# SCH_555__2022-11-10.net
KiCad netlist of a schematic drawn in EasyEDA
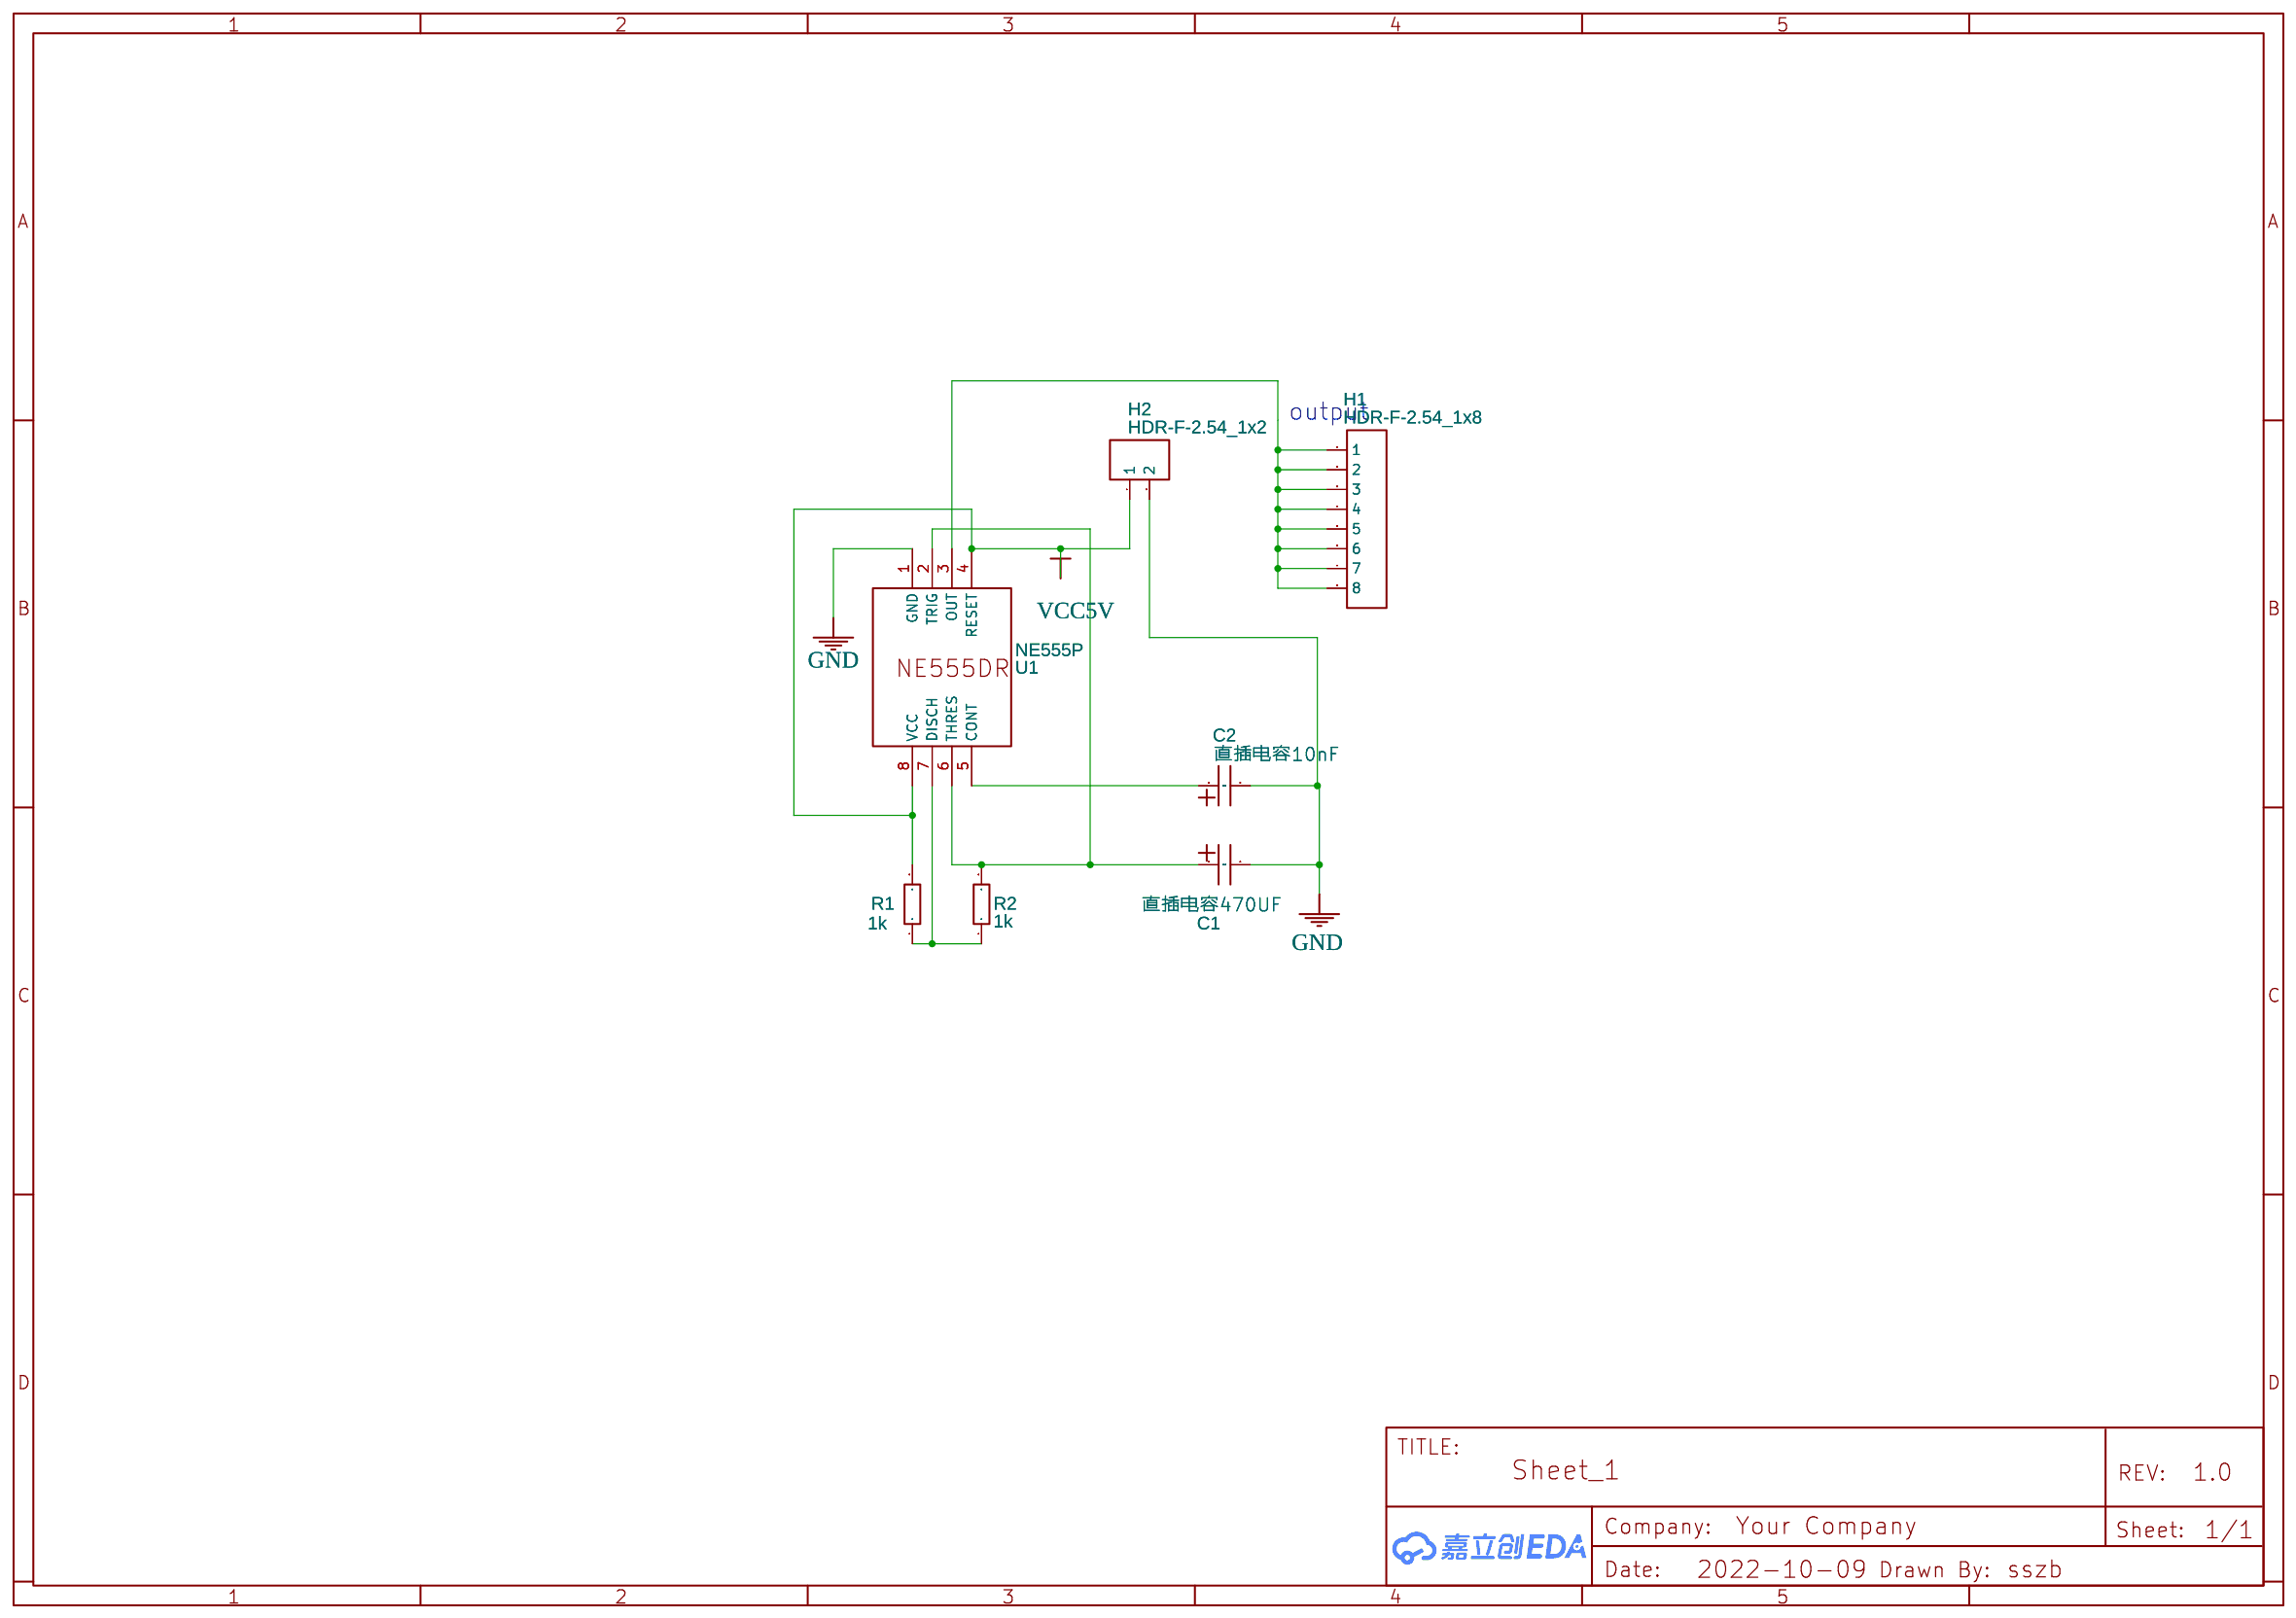
[diagram p0: schematic sheet]

(export (version "E")
  (design (tool "Eeschema 10.0.6"))
  (components
    (comp (ref "C1") (value "直插电容470UF") (libsource (lib "") (part "直插电容470UF_1")))
    (comp (ref "C2") (value "直插电容10nF") (libsource (lib "") (part "直插电容470UF")))
    (comp (ref "H1")
      (value "HDR-F-2.54_1x8")
      (fields (field (name "BOM_Supplier Part") "C225505"))
      (libsource (lib "") (part "HDR-F-2.54_1x8"))
    )
    (comp (ref "H2")
      (value "HDR-F-2.54_1x2")
      (fields (field (name "BOM_Supplier Part") "C49661"))
      (libsource (lib "") (part "HDR-F-2.54_1x2"))
    )
    (comp (ref "R1")
      (value "1k")
      (fields
        (field (name "BOM_Manufacturer Part") "CFR0W4J0681A50")
        (field (name "BOM_Supplier Part") "C70784")
      )
      (libsource (lib "") (part "直插电阻"))
    )
    (comp (ref "R2")
      (value "1k")
      (fields
        (field (name "BOM_Manufacturer Part") "CFR0W4J0681A50")
        (field (name "BOM_Supplier Part") "C70784")
      )
      (libsource (lib "") (part "直插电阻"))
    )
    (comp (ref "U1") (value "NE555P") (libsource (lib "") (part "NE555P")))
  )
  (nets
    (net (code "1") (name "GND") (class "Default")
      (node (ref "C1") (pin "2") (pinfunction "2_2") (pintype "unspecified"))
      (node (ref "C2") (pin "2") (pinfunction "2_2") (pintype "unspecified"))
      (node (ref "H2") (pin "2") (pinfunction "2_2") (pintype "input"))
      (node (ref "U1") (pin "1") (pinfunction "GND_1") (pintype "unspecified"))
    )
    (net (code "2") (name "Net-(U1-CONT)") (class "Default")
      (node (ref "C2") (pin "1") (pinfunction "1_1") (pintype "unspecified"))
      (node (ref "U1") (pin "5") (pinfunction "CONT_5") (pintype "unspecified"))
    )
    (net (code "3") (name "Net-(U1-DISCH)") (class "Default")
      (node (ref "R1") (pin "1") (pinfunction "1_1") (pintype "input"))
      (node (ref "R2") (pin "1") (pinfunction "1_1") (pintype "input"))
      (node (ref "U1") (pin "7") (pinfunction "DISCH_7") (pintype "unspecified"))
    )
    (net (code "4") (name "Net-(U1-OUT)") (class "Default")
      (node (ref "H1") (pin "1") (pinfunction "1_1") (pintype "unspecified"))
      (node (ref "H1") (pin "2") (pinfunction "2_2") (pintype "unspecified"))
      (node (ref "H1") (pin "3") (pinfunction "3_3") (pintype "unspecified"))
      (node (ref "H1") (pin "4") (pinfunction "4_4") (pintype "unspecified"))
      (node (ref "H1") (pin "5") (pinfunction "5_5") (pintype "unspecified"))
      (node (ref "H1") (pin "6") (pinfunction "6_6") (pintype "unspecified"))
      (node (ref "H1") (pin "7") (pinfunction "7_7") (pintype "unspecified"))
      (node (ref "H1") (pin "8") (pinfunction "8_8") (pintype "unspecified"))
      (node (ref "U1") (pin "3") (pinfunction "OUT_3") (pintype "unspecified"))
    )
    (net (code "5") (name "Net-(U1-THRES)") (class "Default")
      (node (ref "C1") (pin "1") (pinfunction "1_1") (pintype "unspecified"))
      (node (ref "R2") (pin "2") (pinfunction "2_2") (pintype "input"))
      (node (ref "U1") (pin "2") (pinfunction "TRIG_2") (pintype "unspecified"))
      (node (ref "U1") (pin "6") (pinfunction "THRES_6") (pintype "unspecified"))
    )
    (net (code "6") (name "VCC5V") (class "Default")
      (node (ref "H2") (pin "1") (pinfunction "1_1") (pintype "input"))
      (node (ref "R1") (pin "2") (pinfunction "2_2") (pintype "input"))
      (node (ref "U1") (pin "4") (pinfunction "RESET_4") (pintype "unspecified"))
      (node (ref "U1") (pin "8") (pinfunction "VCC_8") (pintype "unspecified"))
    )
  )
)
